# Sheet1.net
KiCad netlist of a schematic drawn in Altium Designer
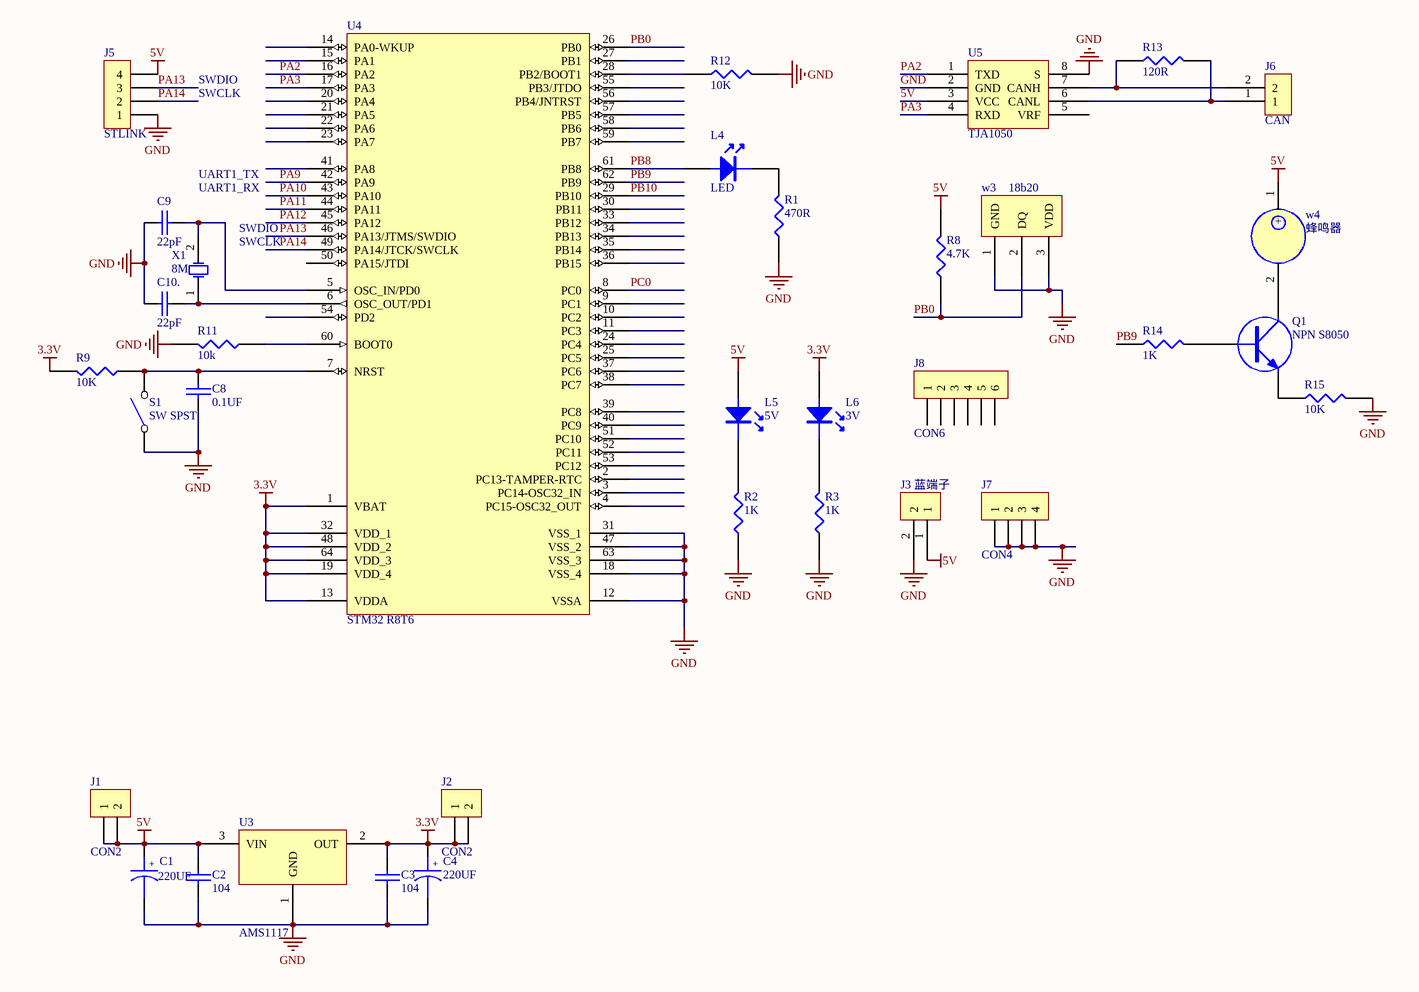
[diagram p0: Sheet1.SchDoc]

(export (version "E")
  (design (tool "Eeschema 10.0.6"))
  (components
    (comp (ref "C1") (value "220UF") (footprint "RB1-2") (libsource (lib "毕设原理图封装库") (part "有极性电容")))
    (comp (ref "C2") (value "104") (footprint "1206") (libsource (lib "毕设原理图封装库") (part "无极性电容")))
    (comp (ref "C3") (value "104") (footprint "1206") (libsource (lib "毕设原理图封装库") (part "无极性电容")))
    (comp (ref "C4") (value "220UF") (footprint "RB1-2") (libsource (lib "毕设原理图封装库") (part "有极性电容")))
    (comp (ref "C8") (value "0.1UF") (footprint "1206") (libsource (lib "毕设原理图封装库") (part "无极性电容")))
    (comp (ref "C9") (value "22pF") (footprint "1206") (libsource (lib "毕设原理图封装库") (part "无极性电容")))
    (comp (ref "C10.") (value "22pF") (footprint "1206") (libsource (lib "毕设原理图封装库") (part "无极性电容")))
    (comp (ref "J1") (value "CON2") (footprint "SIP2") (libsource (lib "毕设原理图封装库") (part "CON2")))
    (comp (ref "J2") (value "CON2") (footprint "SIP2") (libsource (lib "毕设原理图封装库") (part "CON2")))
    (comp (ref "J3") (value "蓝端子") (footprint "蓝端子") (libsource (lib "") (part "蓝端子_1")))
    (comp (ref "J5") (value "STLINK") (footprint "SIP4") (libsource (lib "") (part "CON4_1")))
    (comp (ref "J6") (value "CAN") (footprint "蓝端子") (libsource (lib "毕设原理图封装库") (part "蓝端子")))
    (comp (ref "J7") (value "CON4") (footprint "SIP4") (libsource (lib "毕设原理图封装库") (part "CON4")))
    (comp (ref "J8") (value "CON6") (footprint "SIP6") (libsource (lib "毕设原理图封装库") (part "CON6")))
    (comp (ref "L4") (value "LED") (footprint "0805") (libsource (lib "毕设原理图封装库") (part "LED")))
    (comp (ref "L5") (value "5V") (footprint "0805") (libsource (lib "毕设原理图封装库") (part "LED")))
    (comp (ref "L6") (value "3V") (footprint "0805") (libsource (lib "毕设原理图封装库") (part "LED")))
    (comp (ref "Q1") (value "NPN S8050") (description "NPN 型三极管") (libsource (lib "毕设原理图封装库") (part "NPN")))
    (comp (ref "R1") (value "470R") (footprint "AXIAL0.4") (libsource (lib "毕设原理图封装库") (part "电阻2")))
    (comp (ref "R2") (value "1K") (footprint "AXIAL0.4") (libsource (lib "毕设原理图封装库") (part "电阻2")))
    (comp (ref "R3") (value "1K") (footprint "AXIAL0.4") (libsource (lib "毕设原理图封装库") (part "电阻2")))
    (comp (ref "R8") (value "4.7K") (footprint "AXIAL0.4") (libsource (lib "毕设原理图封装库") (part "电阻2")))
    (comp (ref "R9") (value "10K") (footprint "AXIAL0.4") (libsource (lib "毕设原理图封装库") (part "电阻2")))
    (comp (ref "R11") (value "10k") (footprint "AXIAL0.4") (libsource (lib "毕设原理图封装库") (part "电阻2")))
    (comp (ref "R12") (value "10K") (footprint "AXIAL0.4") (libsource (lib "毕设原理图封装库") (part "电阻2")))
    (comp (ref "R13") (value "120R") (footprint "AXIAL0.4") (libsource (lib "毕设原理图封装库") (part "电阻2")))
    (comp (ref "R14") (value "1K") (footprint "AXIAL0.4") (libsource (lib "毕设原理图封装库") (part "电阻2")))
    (comp (ref "R15") (value "10K") (footprint "AXIAL0.4") (libsource (lib "毕设原理图封装库") (part "电阻2")))
    (comp (ref "S1") (value "SW SPST") (description "单刀单掷开关") (libsource (lib "毕设原理图封装库") (part "SW SPST")))
    (comp (ref "U3") (value "AMS1117") (footprint "AMS117") (libsource (lib "毕设原理图封装库") (part "AMS1117")))
    (comp (ref "U4")
      (value "STM32 R8T6")
      (footprint "STM32   64")
      (libsource (lib "毕设原理图封装库") (part "STM32 R8T6"))
    )
    (comp (ref "U5") (value "TJA1050") (libsource (lib "毕设原理图封装库") (part "TJA1050")))
    (comp (ref "w3") (value "18b20") (libsource (lib "毕设原理图封装库") (part "18b20")))
    (comp (ref "w4") (value "蜂鸣器") (libsource (lib "毕设原理图封装库") (part "蜂鸣器")))
    (comp (ref "X1")
      (value "8M")
      (footprint "SMD49S")
      (description "Crystal Oscillator")
      (fields (field (name "PUBLISHER") "ZL_A0OFFICE"))
      (libsource (lib "CommomDevices") (part "XTAL_SMD"))
    )
  )
  (nets
    (net (code "1") (name "/PA2") (class "Default")
      (node (ref "U4") (pin "16") (pinfunction "PA2_16") (pintype "bidirectional"))
      (node (ref "U5") (pin "1") (pinfunction "TXD_1") (pintype "passive"))
    )
    (net (code "2") (name "/PA3") (class "Default")
      (node (ref "U4") (pin "17") (pinfunction "PA3_17") (pintype "bidirectional"))
      (node (ref "U5") (pin "4") (pinfunction "RXD_4") (pintype "passive"))
    )
    (net (code "3") (name "/PA9") (class "Default")
      (node (ref "U4") (pin "42") (pinfunction "PA9_42") (pintype "bidirectional"))
    )
    (net (code "4") (name "/PA10") (class "Default")
      (node (ref "U4") (pin "43") (pinfunction "PA10_43") (pintype "bidirectional"))
    )
    (net (code "5") (name "/PA11") (class "Default")
      (node (ref "U4") (pin "44") (pinfunction "PA11_44") (pintype "bidirectional"))
    )
    (net (code "6") (name "/PA12") (class "Default")
      (node (ref "U4") (pin "45") (pinfunction "PA12_45") (pintype "bidirectional"))
    )
    (net (code "7") (name "/PA13") (class "Default")
      (node (ref "J5") (pin "3") (pinfunction "3_3") (pintype "passive"))
      (node (ref "U4") (pin "46") (pinfunction "PA13/JTMS/SWDIO_46") (pintype "bidirectional"))
    )
    (net (code "8") (name "/PA14") (class "Default")
      (node (ref "J5") (pin "2") (pinfunction "2_2") (pintype "passive"))
      (node (ref "U4") (pin "49") (pinfunction "PA14/JTCK/SWCLK_49") (pintype "bidirectional"))
    )
    (net (code "9") (name "/PB0") (class "Default")
      (node (ref "R8") (pin "1") (pinfunction "1_1") (pintype "passive"))
      (node (ref "U4") (pin "26") (pinfunction "PB0_26") (pintype "bidirectional"))
      (node (ref "w3") (pin "2") (pinfunction "DQ_2") (pintype "passive"))
    )
    (net (code "10") (name "/PB8") (class "Default")
      (node (ref "L4") (pin "2") (pinfunction "1_2") (pintype "passive"))
      (node (ref "U4") (pin "61") (pinfunction "PB8_61") (pintype "bidirectional"))
    )
    (net (code "11") (name "/PB9") (class "Default")
      (node (ref "R14") (pin "1") (pinfunction "1_1") (pintype "passive"))
      (node (ref "U4") (pin "62") (pinfunction "PB9_62") (pintype "bidirectional"))
    )
    (net (code "12") (name "/PB10") (class "Default")
      (node (ref "U4") (pin "29") (pinfunction "PB10_29") (pintype "bidirectional"))
    )
    (net (code "13") (name "/PC0") (class "Default")
      (node (ref "U4") (pin "8") (pinfunction "PC0_8") (pintype "bidirectional"))
    )
    (net (code "14") (name "3.3V") (class "Default")
      (node (ref "C3") (pin "1") (pinfunction "1_1") (pintype "passive"))
      (node (ref "C4") (pin "1") (pinfunction "1_1") (pintype "passive"))
      (node (ref "J2") (pin "1") (pinfunction "1_1") (pintype "passive"))
      (node (ref "J2") (pin "2") (pinfunction "2_2") (pintype "passive"))
      (node (ref "L6") (pin "2") (pinfunction "1_2") (pintype "passive"))
      (node (ref "R9") (pin "2") (pinfunction "2_2") (pintype "passive"))
      (node (ref "U3") (pin "2") (pinfunction "OUT_2") (pintype "passive"))
      (node (ref "U4") (pin "1") (pinfunction "VBAT_1") (pintype "power_in"))
      (node (ref "U4") (pin "13") (pinfunction "VDDA_13") (pintype "power_in"))
      (node (ref "U4") (pin "19") (pinfunction "VDD_4_19") (pintype "power_in"))
      (node (ref "U4") (pin "32") (pinfunction "VDD_1_32") (pintype "power_in"))
      (node (ref "U4") (pin "48") (pinfunction "VDD_2_48") (pintype "power_in"))
      (node (ref "U4") (pin "64") (pinfunction "VDD_3_64") (pintype "power_in"))
    )
    (net (code "15") (name "5V") (class "Default")
      (node (ref "C1") (pin "1") (pinfunction "1_1") (pintype "passive"))
      (node (ref "C2") (pin "1") (pinfunction "1_1") (pintype "passive"))
      (node (ref "J1") (pin "1") (pinfunction "1_1") (pintype "passive"))
      (node (ref "J1") (pin "2") (pinfunction "2_2") (pintype "passive"))
      (node (ref "J3") (pin "1") (pinfunction "1_1") (pintype "passive"))
      (node (ref "J5") (pin "4") (pinfunction "4_4") (pintype "passive"))
      (node (ref "L5") (pin "2") (pinfunction "1_2") (pintype "passive"))
      (node (ref "R8") (pin "2") (pinfunction "2_2") (pintype "passive"))
      (node (ref "U3") (pin "3") (pinfunction "VIN_3") (pintype "passive"))
      (node (ref "U5") (pin "3") (pinfunction "VCC_3") (pintype "passive"))
      (node (ref "w4") (pin "1") (pinfunction "+_1") (pintype "passive"))
    )
    (net (code "16") (name "GND") (class "Default")
      (node (ref "C1") (pin "2") (pinfunction "2_2") (pintype "passive"))
      (node (ref "C10.") (pin "1") (pinfunction "1_1") (pintype "passive"))
      (node (ref "C2") (pin "2") (pinfunction "2_2") (pintype "passive"))
      (node (ref "C3") (pin "2") (pinfunction "2_2") (pintype "passive"))
      (node (ref "C4") (pin "2") (pinfunction "2_2") (pintype "passive"))
      (node (ref "C8") (pin "2") (pinfunction "2_2") (pintype "passive"))
      (node (ref "C9") (pin "1") (pinfunction "1_1") (pintype "passive"))
      (node (ref "J3") (pin "2") (pinfunction "2_2") (pintype "passive"))
      (node (ref "J5") (pin "1") (pinfunction "1_1") (pintype "passive"))
      (node (ref "J7") (pin "1") (pinfunction "1_1") (pintype "passive"))
      (node (ref "J7") (pin "2") (pinfunction "2_2") (pintype "passive"))
      (node (ref "J7") (pin "3") (pinfunction "3_3") (pintype "passive"))
      (node (ref "J7") (pin "4") (pinfunction "4_4") (pintype "passive"))
      (node (ref "R1") (pin "1") (pinfunction "1_1") (pintype "passive"))
      (node (ref "R11") (pin "2") (pinfunction "2_2") (pintype "passive"))
      (node (ref "R12") (pin "2") (pinfunction "2_2") (pintype "passive"))
      (node (ref "R15") (pin "2") (pinfunction "2_2") (pintype "passive"))
      (node (ref "R2") (pin "1") (pinfunction "1_1") (pintype "passive"))
      (node (ref "R3") (pin "1") (pinfunction "1_1") (pintype "passive"))
      (node (ref "S1") (pin "1") (pinfunction "COMMON_1") (pintype "passive"))
      (node (ref "U3") (pin "1") (pinfunction "GND_1") (pintype "passive"))
      (node (ref "U4") (pin "12") (pinfunction "VSSA_12") (pintype "power_in"))
      (node (ref "U4") (pin "18") (pinfunction "VSS_4_18") (pintype "power_in"))
      (node (ref "U4") (pin "31") (pinfunction "VSS_1_31") (pintype "power_in"))
      (node (ref "U4") (pin "47") (pinfunction "VSS_2_47") (pintype "power_in"))
      (node (ref "U4") (pin "63") (pinfunction "VSS_3_63") (pintype "power_in"))
      (node (ref "U5") (pin "2") (pinfunction "GND_2") (pintype "passive"))
      (node (ref "U5") (pin "8") (pinfunction "S_8") (pintype "passive"))
      (node (ref "w3") (pin "1") (pinfunction "GND_1") (pintype "passive"))
      (node (ref "w3") (pin "3") (pinfunction "VDD_3") (pintype "passive"))
    )
    (net (code "17") (name "Net-(L4-2)") (class "Default")
      (node (ref "L4") (pin "1") (pinfunction "2_1") (pintype "passive"))
      (node (ref "R1") (pin "2") (pinfunction "2_2") (pintype "passive"))
    )
    (net (code "18") (name "Net-(L5-2)") (class "Default")
      (node (ref "L5") (pin "1") (pinfunction "2_1") (pintype "passive"))
      (node (ref "R2") (pin "2") (pinfunction "2_2") (pintype "passive"))
    )
    (net (code "19") (name "Net-(L6-2)") (class "Default")
      (node (ref "L6") (pin "1") (pinfunction "2_1") (pintype "passive"))
      (node (ref "R3") (pin "2") (pinfunction "2_2") (pintype "passive"))
    )
    (net (code "20") (name "Net-(Q1-B)") (class "Default")
      (node (ref "Q1") (pin "1") (pinfunction "B_1") (pintype "passive"))
      (node (ref "R14") (pin "2") (pinfunction "2_2") (pintype "passive"))
    )
    (net (code "21") (name "Net-(Q1-C)") (class "Default")
      (node (ref "Q1") (pin "2") (pinfunction "C_2") (pintype "passive"))
      (node (ref "w4") (pin "2") (pintype "passive"))
    )
    (net (code "22") (name "Net-(Q1-E)") (class "Default")
      (node (ref "Q1") (pin "3") (pinfunction "E_3") (pintype "passive"))
      (node (ref "R15") (pin "1") (pinfunction "1_1") (pintype "passive"))
    )
    (net (code "23") (name "Net-(S1-NO)") (class "Default")
      (node (ref "C8") (pin "1") (pinfunction "1_1") (pintype "passive"))
      (node (ref "R9") (pin "1") (pinfunction "1_1") (pintype "passive"))
      (node (ref "S1") (pin "2") (pinfunction "NO_2") (pintype "passive"))
      (node (ref "U4") (pin "7") (pinfunction "NRST_7") (pintype "bidirectional"))
    )
    (net (code "24") (name "Net-(U4-BOOT0)") (class "Default")
      (node (ref "R11") (pin "1") (pinfunction "1_1") (pintype "passive"))
      (node (ref "U4") (pin "60") (pinfunction "BOOT0_60") (pintype "input"))
    )
    (net (code "25") (name "Net-(U4-OSC_IN{slash}PD0)") (class "Default")
      (node (ref "C9") (pin "2") (pinfunction "2_2") (pintype "passive"))
      (node (ref "U4") (pin "5") (pinfunction "OSC_IN/PD0_5") (pintype "input"))
      (node (ref "X1") (pin "2") (pinfunction "2_2") (pintype "passive"))
    )
    (net (code "26") (name "Net-(U4-OSC_OUT{slash}PD1)") (class "Default")
      (node (ref "C10.") (pin "2") (pinfunction "2_2") (pintype "passive"))
      (node (ref "U4") (pin "6") (pinfunction "OSC_OUT/PD1_6") (pintype "output"))
      (node (ref "X1") (pin "1") (pinfunction "1_1") (pintype "passive"))
    )
    (net (code "27") (name "Net-(U4-PB2{slash}BOOT1)") (class "Default")
      (node (ref "R12") (pin "1") (pinfunction "1_1") (pintype "passive"))
      (node (ref "U4") (pin "28") (pinfunction "PB2/BOOT1_28") (pintype "bidirectional"))
    )
    (net (code "28") (name "Net-(U5-CANH)") (class "Default")
      (node (ref "J6") (pin "2") (pinfunction "2_2") (pintype "passive"))
      (node (ref "R13") (pin "1") (pinfunction "1_1") (pintype "passive"))
      (node (ref "U5") (pin "7") (pinfunction "CANH_7") (pintype "passive"))
    )
    (net (code "29") (name "Net-(U5-CANL)") (class "Default")
      (node (ref "J6") (pin "1") (pinfunction "1_1") (pintype "passive"))
      (node (ref "R13") (pin "2") (pinfunction "2_2") (pintype "passive"))
      (node (ref "U5") (pin "6") (pinfunction "CANL_6") (pintype "passive"))
    )
    (net (code "30") (name "unconnected-(J8-Pad1)") (class "Default")
      (node (ref "J8") (pin "1") (pinfunction "1_1") (pintype "passive"))
    )
    (net (code "31") (name "unconnected-(J8-Pad2)") (class "Default")
      (node (ref "J8") (pin "2") (pinfunction "2_2") (pintype "passive"))
    )
    (net (code "32") (name "unconnected-(J8-Pad3)") (class "Default")
      (node (ref "J8") (pin "3") (pinfunction "3_3") (pintype "passive"))
    )
    (net (code "33") (name "unconnected-(J8-Pad4)") (class "Default")
      (node (ref "J8") (pin "4") (pinfunction "4_4") (pintype "passive"))
    )
    (net (code "34") (name "unconnected-(J8-Pad5)") (class "Default")
      (node (ref "J8") (pin "5") (pinfunction "5_5") (pintype "passive"))
    )
    (net (code "35") (name "unconnected-(J8-Pad6)") (class "Default")
      (node (ref "J8") (pin "6") (pinfunction "6_6") (pintype "passive"))
    )
    (net (code "36") (name "unconnected-(U4-PA0-WKUP-Pad14)") (class "Default")
      (node (ref "U4") (pin "14") (pinfunction "PA0-WKUP_14") (pintype "bidirectional"))
    )
    (net (code "37") (name "unconnected-(U4-PA1-Pad15)") (class "Default")
      (node (ref "U4") (pin "15") (pinfunction "PA1_15") (pintype "bidirectional"))
    )
    (net (code "38") (name "unconnected-(U4-PA4-Pad20)") (class "Default")
      (node (ref "U4") (pin "20") (pinfunction "PA4_20") (pintype "bidirectional"))
    )
    (net (code "39") (name "unconnected-(U4-PA5-Pad21)") (class "Default")
      (node (ref "U4") (pin "21") (pinfunction "PA5_21") (pintype "bidirectional"))
    )
    (net (code "40") (name "unconnected-(U4-PA6-Pad22)") (class "Default")
      (node (ref "U4") (pin "22") (pinfunction "PA6_22") (pintype "bidirectional"))
    )
    (net (code "41") (name "unconnected-(U4-PA7-Pad23)") (class "Default")
      (node (ref "U4") (pin "23") (pinfunction "PA7_23") (pintype "bidirectional"))
    )
    (net (code "42") (name "unconnected-(U4-PA8-Pad41)") (class "Default")
      (node (ref "U4") (pin "41") (pinfunction "PA8_41") (pintype "bidirectional"))
    )
    (net (code "43") (name "unconnected-(U4-PA15{slash}JTDI-Pad50)") (class "Default")
      (node (ref "U4") (pin "50") (pinfunction "PA15/JTDI_50") (pintype "bidirectional"))
    )
    (net (code "44") (name "unconnected-(U4-PB1-Pad27)") (class "Default")
      (node (ref "U4") (pin "27") (pinfunction "PB1_27") (pintype "bidirectional"))
    )
    (net (code "45") (name "unconnected-(U4-PB3{slash}JTDO-Pad55)") (class "Default")
      (node (ref "U4") (pin "55") (pinfunction "PB3/JTDO_55") (pintype "bidirectional"))
    )
    (net (code "46") (name "unconnected-(U4-PB4{slash}JNTRST-Pad56)") (class "Default")
      (node (ref "U4") (pin "56") (pinfunction "PB4/JNTRST_56") (pintype "bidirectional"))
    )
    (net (code "47") (name "unconnected-(U4-PB5-Pad57)") (class "Default")
      (node (ref "U4") (pin "57") (pinfunction "PB5_57") (pintype "bidirectional"))
    )
    (net (code "48") (name "unconnected-(U4-PB6-Pad58)") (class "Default")
      (node (ref "U4") (pin "58") (pinfunction "PB6_58") (pintype "bidirectional"))
    )
    (net (code "49") (name "unconnected-(U4-PB7-Pad59)") (class "Default")
      (node (ref "U4") (pin "59") (pinfunction "PB7_59") (pintype "bidirectional"))
    )
    (net (code "50") (name "unconnected-(U4-PB11-Pad30)") (class "Default")
      (node (ref "U4") (pin "30") (pinfunction "PB11_30") (pintype "bidirectional"))
    )
    (net (code "51") (name "unconnected-(U4-PB12-Pad33)") (class "Default")
      (node (ref "U4") (pin "33") (pinfunction "PB12_33") (pintype "bidirectional"))
    )
    (net (code "52") (name "unconnected-(U4-PB13-Pad34)") (class "Default")
      (node (ref "U4") (pin "34") (pinfunction "PB13_34") (pintype "bidirectional"))
    )
    (net (code "53") (name "unconnected-(U4-PB14-Pad35)") (class "Default")
      (node (ref "U4") (pin "35") (pinfunction "PB14_35") (pintype "bidirectional"))
    )
    (net (code "54") (name "unconnected-(U4-PB15-Pad36)") (class "Default")
      (node (ref "U4") (pin "36") (pinfunction "PB15_36") (pintype "bidirectional"))
    )
    (net (code "55") (name "unconnected-(U4-PC1-Pad9)") (class "Default")
      (node (ref "U4") (pin "9") (pinfunction "PC1_9") (pintype "bidirectional"))
    )
    (net (code "56") (name "unconnected-(U4-PC2-Pad10)") (class "Default")
      (node (ref "U4") (pin "10") (pinfunction "PC2_10") (pintype "bidirectional"))
    )
    (net (code "57") (name "unconnected-(U4-PC3-Pad11)") (class "Default")
      (node (ref "U4") (pin "11") (pinfunction "PC3_11") (pintype "bidirectional"))
    )
    (net (code "58") (name "unconnected-(U4-PC4-Pad24)") (class "Default")
      (node (ref "U4") (pin "24") (pinfunction "PC4_24") (pintype "bidirectional"))
    )
    (net (code "59") (name "unconnected-(U4-PC5-Pad25)") (class "Default")
      (node (ref "U4") (pin "25") (pinfunction "PC5_25") (pintype "bidirectional"))
    )
    (net (code "60") (name "unconnected-(U4-PC6-Pad37)") (class "Default")
      (node (ref "U4") (pin "37") (pinfunction "PC6_37") (pintype "bidirectional"))
    )
    (net (code "61") (name "unconnected-(U4-PC7-Pad38)") (class "Default")
      (node (ref "U4") (pin "38") (pinfunction "PC7_38") (pintype "bidirectional"))
    )
    (net (code "62") (name "unconnected-(U4-PC8-Pad39)") (class "Default")
      (node (ref "U4") (pin "39") (pinfunction "PC8_39") (pintype "bidirectional"))
    )
    (net (code "63") (name "unconnected-(U4-PC9-Pad40)") (class "Default")
      (node (ref "U4") (pin "40") (pinfunction "PC9_40") (pintype "bidirectional"))
    )
    (net (code "64") (name "unconnected-(U4-PC10-Pad51)") (class "Default")
      (node (ref "U4") (pin "51") (pinfunction "PC10_51") (pintype "bidirectional"))
    )
    (net (code "65") (name "unconnected-(U4-PC11-Pad52)") (class "Default")
      (node (ref "U4") (pin "52") (pinfunction "PC11_52") (pintype "bidirectional"))
    )
    (net (code "66") (name "unconnected-(U4-PC12-Pad53)") (class "Default")
      (node (ref "U4") (pin "53") (pinfunction "PC12_53") (pintype "bidirectional"))
    )
    (net (code "67") (name "unconnected-(U4-PC13-TAMPER-RTC-Pad2)") (class "Default")
      (node (ref "U4") (pin "2") (pinfunction "PC13-TAMPER-RTC_2") (pintype "bidirectional"))
    )
    (net (code "68") (name "unconnected-(U4-PC14-OSC32_IN-Pad3)") (class "Default")
      (node (ref "U4") (pin "3") (pinfunction "PC14-OSC32_IN_3") (pintype "bidirectional"))
    )
    (net (code "69") (name "unconnected-(U4-PC15-OSC32_OUT-Pad4)") (class "Default")
      (node (ref "U4") (pin "4") (pinfunction "PC15-OSC32_OUT_4") (pintype "bidirectional"))
    )
    (net (code "70") (name "unconnected-(U4-PD2-Pad54)") (class "Default")
      (node (ref "U4") (pin "54") (pinfunction "PD2_54") (pintype "bidirectional"))
    )
    (net (code "71") (name "unconnected-(U5-VRF-Pad5)") (class "Default")
      (node (ref "U5") (pin "5") (pinfunction "VRF_5") (pintype "passive"))
    )
  )
)
